# NE555.net
KiCad netlist of a schematic drawn in EasyEDA Pro
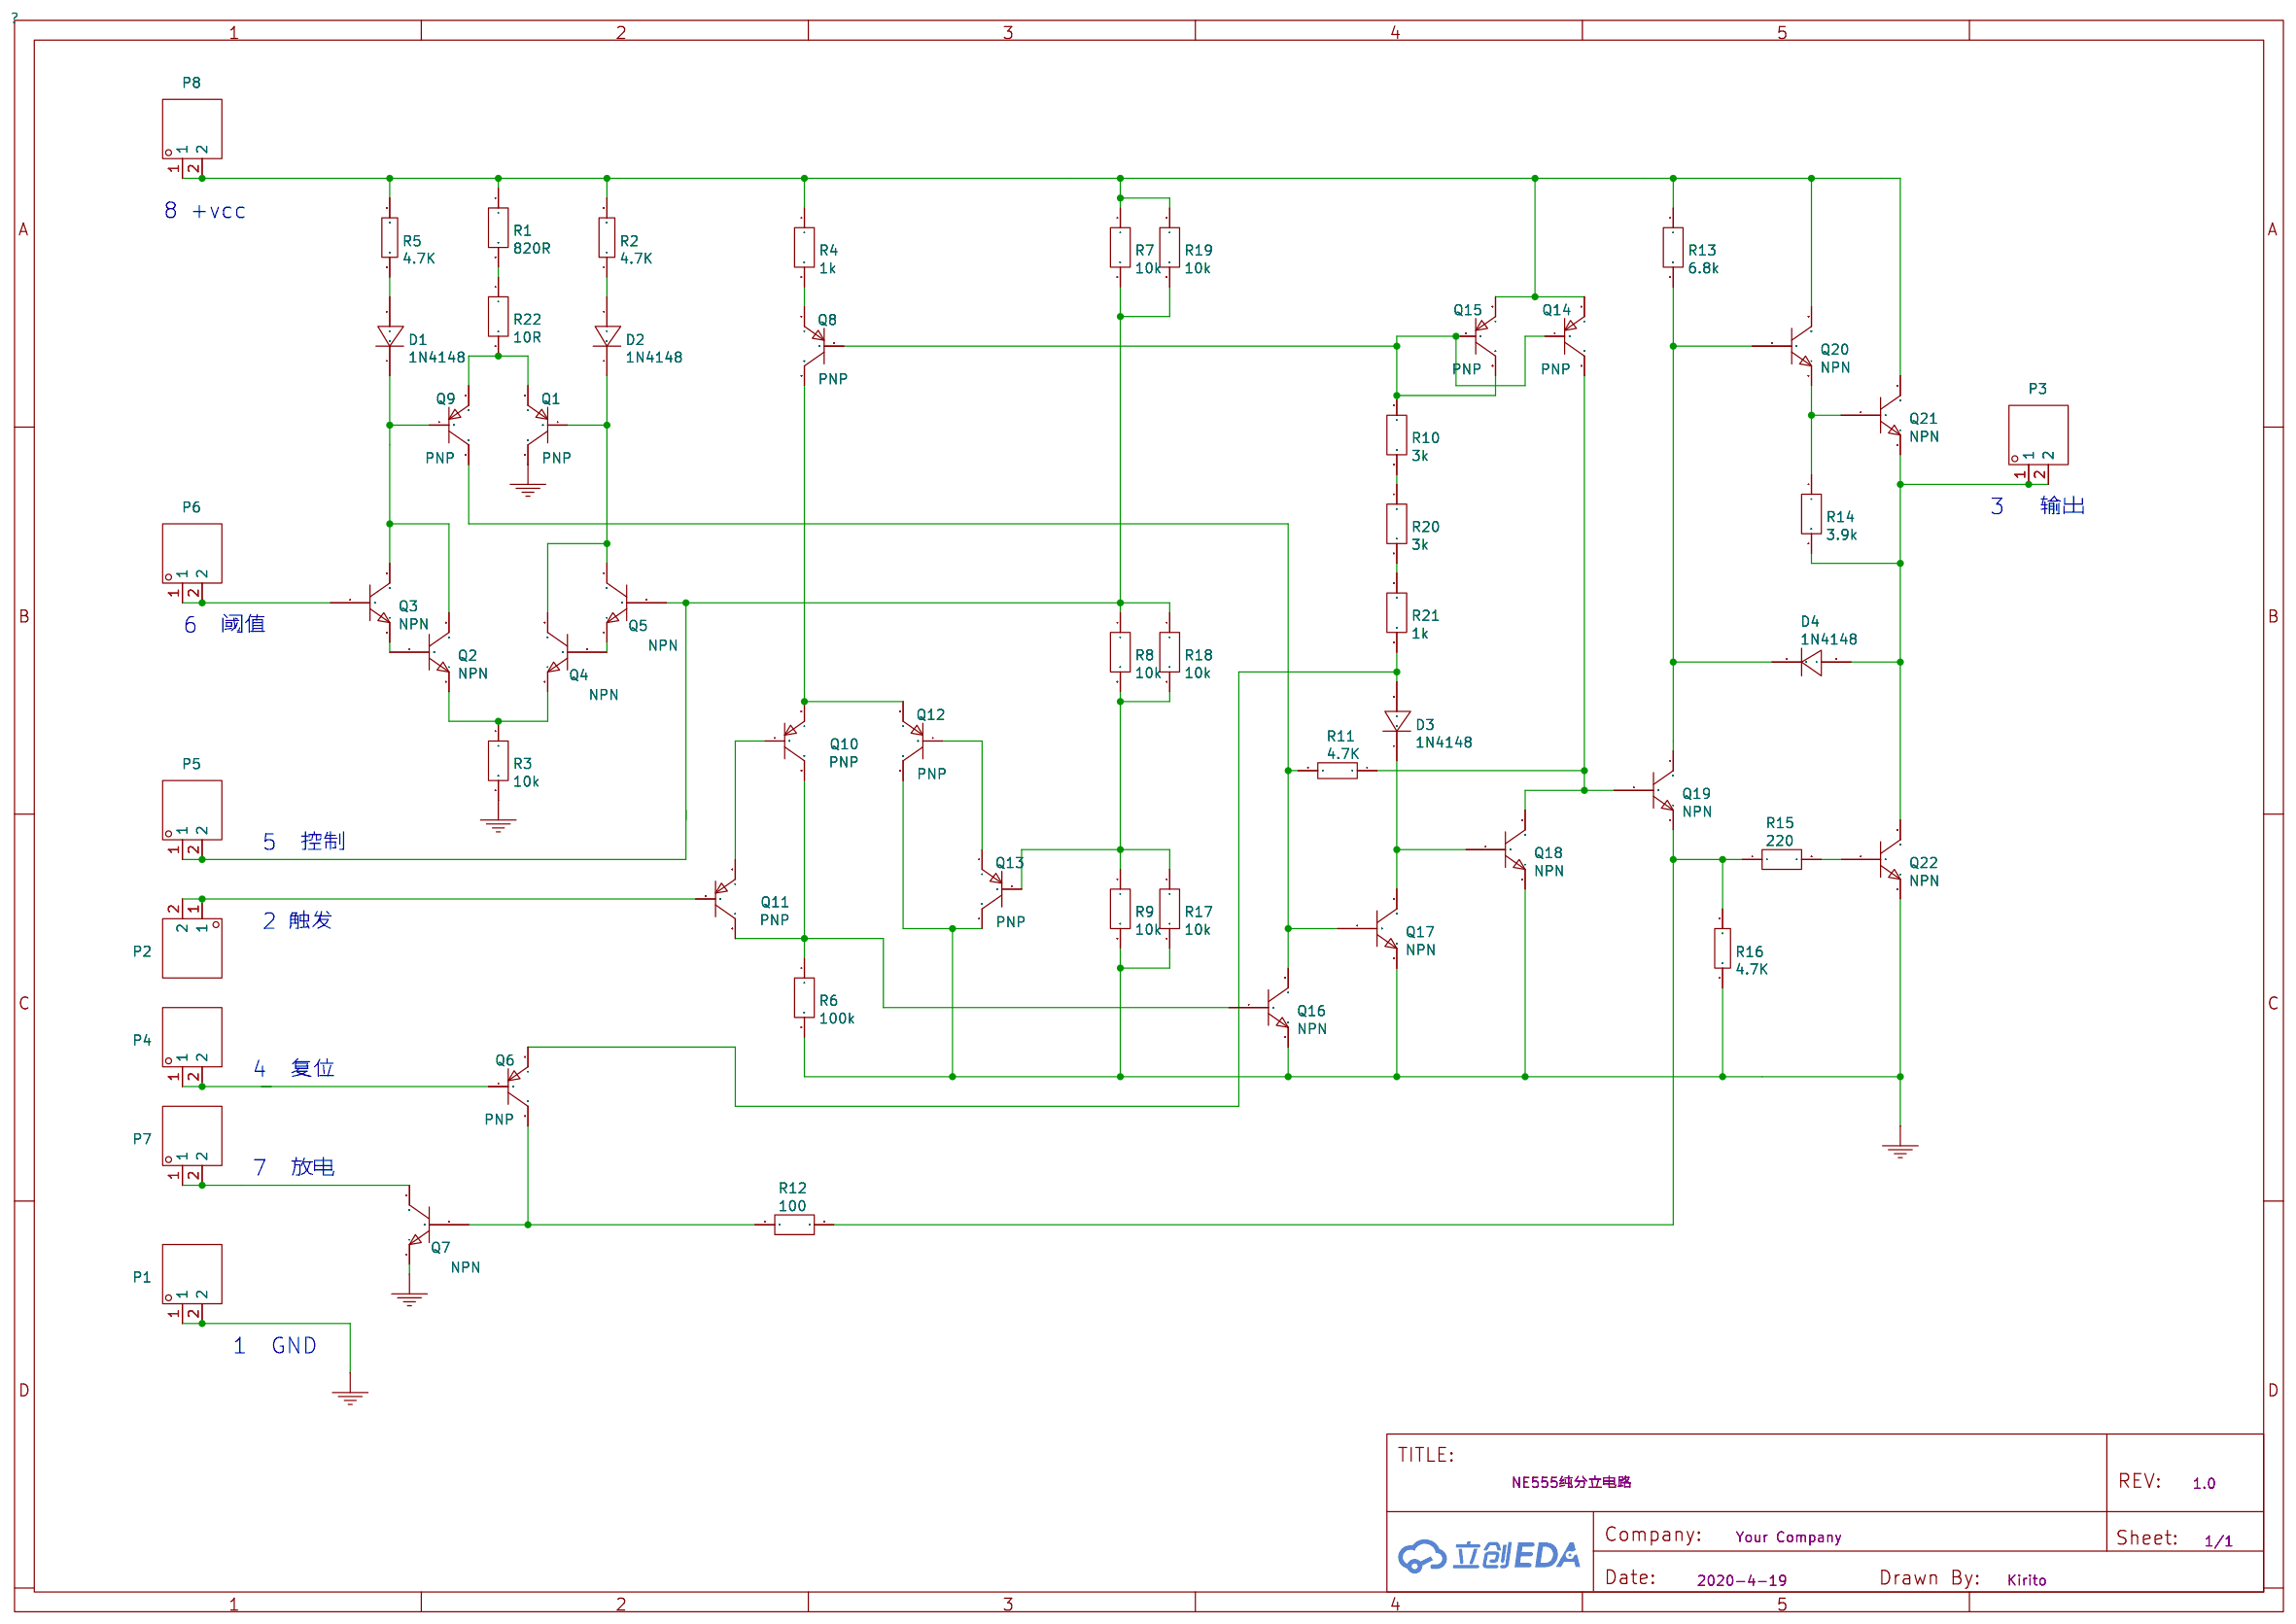
[diagram p0: schematic sheet]

(export (version "E")
  (design (tool "Eeschema 10.0.6"))
  (components
    (comp (ref "D1")
      (value "1N4148")
      (footprint "easyedapro:SOD-523_L1.2-W0.8-LS1.6-RD")
      (libsource (lib "easyedapro") (part "1N4148"))
    )
    (comp (ref "D2")
      (value "1N4148")
      (footprint "easyedapro:SOD-523_L1.2-W0.8-LS1.6-RD")
      (libsource (lib "easyedapro") (part "1N4148"))
    )
    (comp (ref "D3")
      (value "1N4148")
      (footprint "easyedapro:SOD-523_L1.2-W0.8-LS1.6-RD")
      (libsource (lib "easyedapro") (part "1N4148"))
    )
    (comp (ref "D4")
      (value "1N4148")
      (footprint "easyedapro:SOD-523_L1.2-W0.8-LS1.6-RD")
      (libsource (lib "easyedapro") (part "1N4148"))
    )
    (comp (ref "P1")
      (value "RE-H022TD-1190 (LF)(SN)")
      (footprint "easyedapro:HDR-TH_2P-P2.54-V")
      (libsource (lib "easyedapro") (part "RE-H022TD-1190 (LF)(SN)"))
    )
    (comp (ref "P2")
      (value "RE-H022TD-1190 (LF)(SN)")
      (footprint "easyedapro:HDR-TH_2P-P2.54-V")
      (libsource (lib "easyedapro") (part "RE-H022TD-1190 (LF)(SN)"))
    )
    (comp (ref "P3")
      (value "RE-H022TD-1190 (LF)(SN)")
      (footprint "easyedapro:HDR-TH_2P-P2.54-V")
      (libsource (lib "easyedapro") (part "RE-H022TD-1190 (LF)(SN)"))
    )
    (comp (ref "P4")
      (value "RE-H022TD-1190 (LF)(SN)")
      (footprint "easyedapro:HDR-TH_2P-P2.54-V")
      (libsource (lib "easyedapro") (part "RE-H022TD-1190 (LF)(SN)"))
    )
    (comp (ref "P5")
      (value "RE-H022TD-1190 (LF)(SN)")
      (footprint "easyedapro:HDR-TH_2P-P2.54-V")
      (libsource (lib "easyedapro") (part "RE-H022TD-1190 (LF)(SN)"))
    )
    (comp (ref "P6")
      (value "RE-H022TD-1190 (LF)(SN)")
      (footprint "easyedapro:HDR-TH_2P-P2.54-V")
      (libsource (lib "easyedapro") (part "RE-H022TD-1190 (LF)(SN)"))
    )
    (comp (ref "P7")
      (value "RE-H022TD-1190 (LF)(SN)")
      (footprint "easyedapro:HDR-TH_2P-P2.54-V")
      (libsource (lib "easyedapro") (part "RE-H022TD-1190 (LF)(SN)"))
    )
    (comp (ref "P8")
      (value "RE-H022TD-1190 (LF)(SN)")
      (footprint "easyedapro:HDR-TH_2P-P2.54-V")
      (libsource (lib "easyedapro") (part "RE-H022TD-1190 (LF)(SN)"))
    )
    (comp (ref "Q1")
      (value "PNP")
      (footprint "easyedapro:SOT-23-3_L2.9-W1.6-P1.90-LS2.8-BR")
      (libsource (lib "") (part "PNP_1"))
    )
    (comp (ref "Q2")
      (value "NPN")
      (footprint "easyedapro:SOT-23-3_L2.9-W1.3-P1.90-LS2.4-BR")
      (libsource (lib "easyedapro") (part "NPN"))
    )
    (comp (ref "Q3")
      (value "NPN")
      (footprint "easyedapro:SOT-23-3_L2.9-W1.3-P1.90-LS2.4-BR")
      (libsource (lib "easyedapro") (part "NPN"))
    )
    (comp (ref "Q4")
      (value "NPN")
      (footprint "easyedapro:SOT-23-3_L2.9-W1.3-P1.90-LS2.4-BR")
      (libsource (lib "") (part "NPN_1"))
    )
    (comp (ref "Q5")
      (value "NPN")
      (footprint "easyedapro:SOT-23-3_L2.9-W1.3-P1.90-LS2.4-BR")
      (libsource (lib "") (part "NPN_1"))
    )
    (comp (ref "Q6")
      (value "PNP")
      (footprint "easyedapro:SOT-23-3_L2.9-W1.6-P1.90-LS2.8-BR")
      (libsource (lib "easyedapro") (part "PNP"))
    )
    (comp (ref "Q7")
      (value "NPN")
      (footprint "easyedapro:SOT-23-3_L2.9-W1.3-P1.90-LS2.4-BR")
      (libsource (lib "") (part "NPN_1"))
    )
    (comp (ref "Q8")
      (value "PNP")
      (footprint "easyedapro:SOT-23-3_L2.9-W1.6-P1.90-LS2.8-BR")
      (libsource (lib "") (part "PNP_1"))
    )
    (comp (ref "Q9")
      (value "PNP")
      (footprint "easyedapro:SOT-23-3_L2.9-W1.6-P1.90-LS2.8-BR")
      (libsource (lib "easyedapro") (part "PNP"))
    )
    (comp (ref "Q10")
      (value "PNP")
      (footprint "easyedapro:SOT-23-3_L2.9-W1.6-P1.90-LS2.8-BR")
      (libsource (lib "easyedapro") (part "PNP"))
    )
    (comp (ref "Q11")
      (value "PNP")
      (footprint "easyedapro:SOT-23-3_L2.9-W1.6-P1.90-LS2.8-BR")
      (libsource (lib "easyedapro") (part "PNP"))
    )
    (comp (ref "Q12")
      (value "PNP")
      (footprint "easyedapro:SOT-23-3_L2.9-W1.6-P1.90-LS2.8-BR")
      (libsource (lib "") (part "PNP_1"))
    )
    (comp (ref "Q13")
      (value "PNP")
      (footprint "easyedapro:SOT-23-3_L2.9-W1.6-P1.90-LS2.8-BR")
      (libsource (lib "") (part "PNP_1"))
    )
    (comp (ref "Q14")
      (value "PNP")
      (footprint "easyedapro:SOT-23-3_L2.9-W1.6-P1.90-LS2.8-BR")
      (libsource (lib "easyedapro") (part "PNP"))
    )
    (comp (ref "Q15")
      (value "PNP")
      (footprint "easyedapro:SOT-23-3_L2.9-W1.6-P1.90-LS2.8-BR")
      (libsource (lib "easyedapro") (part "PNP"))
    )
    (comp (ref "Q16")
      (value "NPN")
      (footprint "easyedapro:SOT-23-3_L2.9-W1.3-P1.90-LS2.4-BR")
      (libsource (lib "easyedapro") (part "NPN"))
    )
    (comp (ref "Q17")
      (value "NPN")
      (footprint "easyedapro:SOT-23-3_L2.9-W1.3-P1.90-LS2.4-BR")
      (libsource (lib "easyedapro") (part "NPN"))
    )
    (comp (ref "Q18")
      (value "NPN")
      (footprint "easyedapro:SOT-23-3_L2.9-W1.3-P1.90-LS2.4-BR")
      (libsource (lib "easyedapro") (part "NPN"))
    )
    (comp (ref "Q19")
      (value "NPN")
      (footprint "easyedapro:SOT-23-3_L2.9-W1.3-P1.90-LS2.4-BR")
      (libsource (lib "easyedapro") (part "NPN"))
    )
    (comp (ref "Q20")
      (value "NPN")
      (footprint "easyedapro:SOT-23-3_L2.9-W1.3-P1.90-LS2.4-BR")
      (libsource (lib "easyedapro") (part "NPN"))
    )
    (comp (ref "Q21")
      (value "NPN")
      (footprint "easyedapro:SOT-23-3_L2.9-W1.3-P1.90-LS2.4-BR")
      (libsource (lib "easyedapro") (part "NPN"))
    )
    (comp (ref "Q22")
      (value "NPN")
      (footprint "easyedapro:SOT-23-3_L2.9-W1.3-P1.90-LS2.4-BR")
      (libsource (lib "easyedapro") (part "NPN"))
    )
    (comp (ref "R1")
      (value "820R")
      (footprint "easyedapro:R0603")
      (libsource (lib "easyedapro") (part "820R"))
    )
    (comp (ref "R2")
      (value "4.7K")
      (footprint "easyedapro:R0603")
      (fields (field (name "Manufacturer Part") "TC0325B4701T5E") (field (name "Manufacturer") "UniOhm"))
      (libsource (lib "easyedapro") (part "4.7K"))
    )
    (comp (ref "R3") (value "10k") (footprint "easyedapro:R0603") (libsource (lib "easyedapro") (part "10k")))
    (comp (ref "R4") (value "1k") (footprint "easyedapro:R0603") (libsource (lib "easyedapro") (part "1k")))
    (comp (ref "R5")
      (value "4.7K")
      (footprint "easyedapro:R0603")
      (fields (field (name "Manufacturer Part") "TC0325B4701T5E") (field (name "Manufacturer") "UniOhm"))
      (libsource (lib "easyedapro") (part "4.7K"))
    )
    (comp (ref "R6")
      (value "100k")
      (footprint "easyedapro:R0603")
      (libsource (lib "easyedapro") (part "100k"))
    )
    (comp (ref "R7") (value "10k") (footprint "easyedapro:R0603") (libsource (lib "easyedapro") (part "10k")))
    (comp (ref "R8") (value "10k") (footprint "easyedapro:R0603") (libsource (lib "easyedapro") (part "10k")))
    (comp (ref "R9") (value "10k") (footprint "easyedapro:R0603") (libsource (lib "easyedapro") (part "10k")))
    (comp (ref "R10") (value "3k") (footprint "easyedapro:R0603") (libsource (lib "easyedapro") (part "3k")))
    (comp (ref "R11")
      (value "4.7K")
      (footprint "easyedapro:R0603")
      (fields (field (name "Manufacturer Part") "TC0325B4701T5E") (field (name "Manufacturer") "UniOhm"))
      (libsource (lib "easyedapro") (part "4.7K"))
    )
    (comp (ref "R12")
      (value "100")
      (footprint "easyedapro:R0603")
      (libsource (lib "easyedapro") (part "100"))
    )
    (comp (ref "R13")
      (value "6.8k")
      (footprint "easyedapro:R0603")
      (libsource (lib "easyedapro") (part "6.8k"))
    )
    (comp (ref "R14")
      (value "3.9k")
      (footprint "easyedapro:R0603")
      (libsource (lib "easyedapro") (part "3.9k"))
    )
    (comp (ref "R15")
      (value "220")
      (footprint "easyedapro:R0603")
      (libsource (lib "easyedapro") (part "220"))
    )
    (comp (ref "R16")
      (value "4.7K")
      (footprint "easyedapro:R0603")
      (fields (field (name "Manufacturer Part") "TC0325B4701T5E") (field (name "Manufacturer") "UniOhm"))
      (libsource (lib "easyedapro") (part "4.7K"))
    )
    (comp (ref "R17")
      (value "10k")
      (footprint "easyedapro:R0603")
      (libsource (lib "easyedapro") (part "10k"))
    )
    (comp (ref "R18")
      (value "10k")
      (footprint "easyedapro:R0603")
      (libsource (lib "easyedapro") (part "10k"))
    )
    (comp (ref "R19")
      (value "10k")
      (footprint "easyedapro:R0603")
      (libsource (lib "easyedapro") (part "10k"))
    )
    (comp (ref "R20") (value "3k") (footprint "easyedapro:R0603") (libsource (lib "easyedapro") (part "3k")))
    (comp (ref "R21") (value "1k") (footprint "easyedapro:R0603") (libsource (lib "easyedapro") (part "1k")))
    (comp (ref "R22")
      (value "10R")
      (footprint "easyedapro:R0603")
      (libsource (lib "easyedapro") (part "10R"))
    )
  )
  (nets
    (net (code "1") (name "GND") (class "Default")
      (node (ref "P1") (pin "1") (pinfunction "1_1") (pintype "unspecified"))
      (node (ref "P1") (pin "2") (pinfunction "2_2") (pintype "unspecified"))
      (node (ref "Q1") (pin "3") (pinfunction "C_3") (pintype "input"))
      (node (ref "Q12") (pin "3") (pinfunction "C_3") (pintype "input"))
      (node (ref "Q13") (pin "3") (pinfunction "C_3") (pintype "input"))
      (node (ref "Q16") (pin "2") (pinfunction "E_2") (pintype "unspecified"))
      (node (ref "Q17") (pin "2") (pinfunction "E_2") (pintype "unspecified"))
      (node (ref "Q18") (pin "2") (pinfunction "E_2") (pintype "unspecified"))
      (node (ref "Q22") (pin "2") (pinfunction "E_2") (pintype "unspecified"))
      (node (ref "Q7") (pin "2") (pinfunction "E_2") (pintype "unspecified"))
      (node (ref "R16") (pin "1") (pinfunction "1_1") (pintype "input"))
      (node (ref "R17") (pin "2") (pinfunction "2_2") (pintype "unspecified"))
      (node (ref "R3") (pin "2") (pinfunction "2_2") (pintype "unspecified"))
      (node (ref "R6") (pin "2") (pinfunction "2_2") (pintype "unspecified"))
      (node (ref "R9") (pin "2") (pinfunction "2_2") (pintype "unspecified"))
    )
    (net (code "2") (name "Net-(D1-A)") (class "Default")
      (node (ref "D1") (pin "2") (pinfunction "A_2") (pintype "unspecified"))
      (node (ref "R5") (pin "1") (pinfunction "1_1") (pintype "input"))
    )
    (net (code "3") (name "Net-(D1-C)") (class "Default")
      (node (ref "D1") (pin "1") (pinfunction "C_1") (pintype "unspecified"))
      (node (ref "Q2") (pin "3") (pinfunction "C_3") (pintype "unspecified"))
      (node (ref "Q3") (pin "3") (pinfunction "C_3") (pintype "unspecified"))
      (node (ref "Q9") (pin "1") (pinfunction "B_1") (pintype "input"))
    )
    (net (code "4") (name "Net-(D2-A)") (class "Default")
      (node (ref "D2") (pin "2") (pinfunction "A_2") (pintype "unspecified"))
      (node (ref "R2") (pin "1") (pinfunction "1_1") (pintype "input"))
    )
    (net (code "5") (name "Net-(D2-C)") (class "Default")
      (node (ref "D2") (pin "1") (pinfunction "C_1") (pintype "unspecified"))
      (node (ref "Q1") (pin "1") (pinfunction "B_1") (pintype "input"))
      (node (ref "Q4") (pin "3") (pinfunction "C_3") (pintype "unspecified"))
      (node (ref "Q5") (pin "3") (pinfunction "C_3") (pintype "unspecified"))
    )
    (net (code "6") (name "Net-(D3-A)") (class "Default")
      (node (ref "D3") (pin "2") (pinfunction "A_2") (pintype "unspecified"))
      (node (ref "Q6") (pin "2") (pinfunction "E_2") (pintype "input"))
      (node (ref "R21") (pin "2") (pinfunction "2_2") (pintype "unspecified"))
    )
    (net (code "7") (name "Net-(D3-C)") (class "Default")
      (node (ref "D3") (pin "1") (pinfunction "C_1") (pintype "unspecified"))
      (node (ref "Q17") (pin "3") (pinfunction "C_3") (pintype "unspecified"))
      (node (ref "Q18") (pin "1") (pinfunction "B_1") (pintype "unspecified"))
    )
    (net (code "8") (name "Net-(D4-A)") (class "Default")
      (node (ref "D4") (pin "2") (pinfunction "A_2") (pintype "unspecified"))
      (node (ref "P3") (pin "1") (pinfunction "1_1") (pintype "unspecified"))
      (node (ref "P3") (pin "2") (pinfunction "2_2") (pintype "unspecified"))
      (node (ref "Q21") (pin "2") (pinfunction "E_2") (pintype "unspecified"))
      (node (ref "Q22") (pin "3") (pinfunction "C_3") (pintype "unspecified"))
      (node (ref "R14") (pin "2") (pinfunction "2_2") (pintype "unspecified"))
    )
    (net (code "9") (name "Net-(D4-C)") (class "Default")
      (node (ref "D4") (pin "1") (pinfunction "C_1") (pintype "unspecified"))
      (node (ref "Q19") (pin "3") (pinfunction "C_3") (pintype "unspecified"))
      (node (ref "Q20") (pin "1") (pinfunction "B_1") (pintype "unspecified"))
      (node (ref "R13") (pin "2") (pinfunction "2_2") (pintype "unspecified"))
    )
    (net (code "10") (name "Net-(Q1-E)") (class "Default")
      (node (ref "Q1") (pin "2") (pinfunction "E_2") (pintype "input"))
      (node (ref "Q9") (pin "2") (pinfunction "E_2") (pintype "input"))
      (node (ref "R22") (pin "2") (pinfunction "2_2") (pintype "unspecified"))
    )
    (net (code "11") (name "Net-(Q2-B)") (class "Default")
      (node (ref "Q2") (pin "1") (pinfunction "B_1") (pintype "unspecified"))
      (node (ref "Q3") (pin "2") (pinfunction "E_2") (pintype "unspecified"))
    )
    (net (code "12") (name "Net-(Q2-E)") (class "Default")
      (node (ref "Q2") (pin "2") (pinfunction "E_2") (pintype "unspecified"))
      (node (ref "Q4") (pin "2") (pinfunction "E_2") (pintype "unspecified"))
      (node (ref "R3") (pin "1") (pinfunction "1_1") (pintype "unspecified"))
    )
    (net (code "13") (name "Net-(Q3-B)") (class "Default")
      (node (ref "P6") (pin "1") (pinfunction "1_1") (pintype "unspecified"))
      (node (ref "P6") (pin "2") (pinfunction "2_2") (pintype "unspecified"))
      (node (ref "Q3") (pin "1") (pinfunction "B_1") (pintype "unspecified"))
    )
    (net (code "14") (name "Net-(Q4-B)") (class "Default")
      (node (ref "Q4") (pin "1") (pinfunction "B_1") (pintype "unspecified"))
      (node (ref "Q5") (pin "2") (pinfunction "E_2") (pintype "unspecified"))
    )
    (net (code "15") (name "Net-(Q5-B)") (class "Default")
      (node (ref "P5") (pin "1") (pinfunction "1_1") (pintype "unspecified"))
      (node (ref "P5") (pin "2") (pinfunction "2_2") (pintype "unspecified"))
      (node (ref "Q5") (pin "1") (pinfunction "B_1") (pintype "unspecified"))
      (node (ref "R18") (pin "1") (pinfunction "1_1") (pintype "unspecified"))
      (node (ref "R19") (pin "2") (pinfunction "2_2") (pintype "unspecified"))
      (node (ref "R7") (pin "2") (pinfunction "2_2") (pintype "unspecified"))
      (node (ref "R8") (pin "1") (pinfunction "1_1") (pintype "unspecified"))
    )
    (net (code "16") (name "Net-(Q6-B)") (class "Default")
      (node (ref "P4") (pin "1") (pinfunction "1_1") (pintype "unspecified"))
      (node (ref "P4") (pin "2") (pinfunction "2_2") (pintype "unspecified"))
      (node (ref "Q6") (pin "1") (pinfunction "B_1") (pintype "input"))
    )
    (net (code "17") (name "Net-(Q6-C)") (class "Default")
      (node (ref "Q6") (pin "3") (pinfunction "C_3") (pintype "input"))
      (node (ref "Q7") (pin "1") (pinfunction "B_1") (pintype "unspecified"))
      (node (ref "R12") (pin "1") (pinfunction "1_1") (pintype "unspecified"))
    )
    (net (code "18") (name "Net-(Q7-C)") (class "Default")
      (node (ref "P7") (pin "1") (pinfunction "1_1") (pintype "unspecified"))
      (node (ref "P7") (pin "2") (pinfunction "2_2") (pintype "unspecified"))
      (node (ref "Q7") (pin "3") (pinfunction "C_3") (pintype "unspecified"))
    )
    (net (code "19") (name "Net-(Q8-E)") (class "Default")
      (node (ref "Q8") (pin "2") (pinfunction "E_2") (pintype "input"))
      (node (ref "R4") (pin "2") (pinfunction "2_2") (pintype "unspecified"))
    )
    (net (code "20") (name "Net-(Q10-B)") (class "Default")
      (node (ref "Q10") (pin "1") (pinfunction "B_1") (pintype "input"))
      (node (ref "Q11") (pin "2") (pinfunction "E_2") (pintype "input"))
    )
    (net (code "21") (name "Net-(Q10-C)") (class "Default")
      (node (ref "Q10") (pin "3") (pinfunction "C_3") (pintype "input"))
      (node (ref "Q11") (pin "3") (pinfunction "C_3") (pintype "input"))
      (node (ref "Q16") (pin "1") (pinfunction "B_1") (pintype "unspecified"))
      (node (ref "R6") (pin "1") (pinfunction "1_1") (pintype "unspecified"))
    )
    (net (code "22") (name "Net-(Q10-E)") (class "Default")
      (node (ref "Q10") (pin "2") (pinfunction "E_2") (pintype "input"))
      (node (ref "Q12") (pin "2") (pinfunction "E_2") (pintype "input"))
      (node (ref "Q8") (pin "3") (pinfunction "C_3") (pintype "input"))
    )
    (net (code "23") (name "Net-(Q11-B)") (class "Default")
      (node (ref "P2") (pin "1") (pinfunction "1_1") (pintype "unspecified"))
      (node (ref "P2") (pin "2") (pinfunction "2_2") (pintype "unspecified"))
      (node (ref "Q11") (pin "1") (pinfunction "B_1") (pintype "input"))
    )
    (net (code "24") (name "Net-(Q12-B)") (class "Default")
      (node (ref "Q12") (pin "1") (pinfunction "B_1") (pintype "input"))
      (node (ref "Q13") (pin "2") (pinfunction "E_2") (pintype "input"))
    )
    (net (code "25") (name "Net-(Q13-B)") (class "Default")
      (node (ref "Q13") (pin "1") (pinfunction "B_1") (pintype "input"))
      (node (ref "R17") (pin "1") (pinfunction "1_1") (pintype "unspecified"))
      (node (ref "R18") (pin "2") (pinfunction "2_2") (pintype "unspecified"))
      (node (ref "R8") (pin "2") (pinfunction "2_2") (pintype "unspecified"))
      (node (ref "R9") (pin "1") (pinfunction "1_1") (pintype "unspecified"))
    )
    (net (code "26") (name "Net-(Q14-B)") (class "Default")
      (node (ref "Q14") (pin "1") (pinfunction "B_1") (pintype "input"))
      (node (ref "Q15") (pin "1") (pinfunction "B_1") (pintype "input"))
      (node (ref "Q15") (pin "3") (pinfunction "C_3") (pintype "input"))
      (node (ref "Q8") (pin "1") (pinfunction "B_1") (pintype "input"))
      (node (ref "R10") (pin "1") (pinfunction "1_1") (pintype "unspecified"))
    )
    (net (code "27") (name "Net-(Q14-C)") (class "Default")
      (node (ref "Q14") (pin "3") (pinfunction "C_3") (pintype "input"))
      (node (ref "Q18") (pin "3") (pinfunction "C_3") (pintype "unspecified"))
      (node (ref "Q19") (pin "1") (pinfunction "B_1") (pintype "unspecified"))
      (node (ref "R11") (pin "1") (pinfunction "1_1") (pintype "input"))
    )
    (net (code "28") (name "Net-(Q14-E)") (class "Default")
      (node (ref "P8") (pin "1") (pinfunction "1_1") (pintype "unspecified"))
      (node (ref "P8") (pin "2") (pinfunction "2_2") (pintype "unspecified"))
      (node (ref "Q14") (pin "2") (pinfunction "E_2") (pintype "input"))
      (node (ref "Q15") (pin "2") (pinfunction "E_2") (pintype "input"))
      (node (ref "Q20") (pin "3") (pinfunction "C_3") (pintype "unspecified"))
      (node (ref "Q21") (pin "3") (pinfunction "C_3") (pintype "unspecified"))
      (node (ref "R1") (pin "1") (pinfunction "1_1") (pintype "unspecified"))
      (node (ref "R13") (pin "1") (pinfunction "1_1") (pintype "unspecified"))
      (node (ref "R19") (pin "1") (pinfunction "1_1") (pintype "unspecified"))
      (node (ref "R2") (pin "2") (pinfunction "2_2") (pintype "input"))
      (node (ref "R4") (pin "1") (pinfunction "1_1") (pintype "unspecified"))
      (node (ref "R5") (pin "2") (pinfunction "2_2") (pintype "input"))
      (node (ref "R7") (pin "1") (pinfunction "1_1") (pintype "unspecified"))
    )
    (net (code "29") (name "Net-(Q16-C)") (class "Default")
      (node (ref "Q16") (pin "3") (pinfunction "C_3") (pintype "unspecified"))
      (node (ref "Q17") (pin "1") (pinfunction "B_1") (pintype "unspecified"))
      (node (ref "Q9") (pin "3") (pinfunction "C_3") (pintype "input"))
      (node (ref "R11") (pin "2") (pinfunction "2_2") (pintype "input"))
    )
    (net (code "30") (name "Net-(Q19-E)") (class "Default")
      (node (ref "Q19") (pin "2") (pinfunction "E_2") (pintype "unspecified"))
      (node (ref "R12") (pin "2") (pinfunction "2_2") (pintype "unspecified"))
      (node (ref "R15") (pin "1") (pinfunction "1_1") (pintype "unspecified"))
      (node (ref "R16") (pin "2") (pinfunction "2_2") (pintype "input"))
    )
    (net (code "31") (name "Net-(Q20-E)") (class "Default")
      (node (ref "Q20") (pin "2") (pinfunction "E_2") (pintype "unspecified"))
      (node (ref "Q21") (pin "1") (pinfunction "B_1") (pintype "unspecified"))
      (node (ref "R14") (pin "1") (pinfunction "1_1") (pintype "unspecified"))
    )
    (net (code "32") (name "Net-(Q22-B)") (class "Default")
      (node (ref "Q22") (pin "1") (pinfunction "B_1") (pintype "unspecified"))
      (node (ref "R15") (pin "2") (pinfunction "2_2") (pintype "unspecified"))
    )
    (net (code "33") (name "Net-(R1-Pad2)") (class "Default")
      (node (ref "R1") (pin "2") (pinfunction "2_2") (pintype "unspecified"))
      (node (ref "R22") (pin "1") (pinfunction "1_1") (pintype "unspecified"))
    )
    (net (code "34") (name "Net-(R10-Pad2)") (class "Default")
      (node (ref "R10") (pin "2") (pinfunction "2_2") (pintype "unspecified"))
      (node (ref "R20") (pin "1") (pinfunction "1_1") (pintype "unspecified"))
    )
    (net (code "35") (name "Net-(R20-Pad2)") (class "Default")
      (node (ref "R20") (pin "2") (pinfunction "2_2") (pintype "unspecified"))
      (node (ref "R21") (pin "1") (pinfunction "1_1") (pintype "unspecified"))
    )
  )
)
